# hacker-boards-refactor.net
KiCad netlist of a schematic drawn in EAGLE
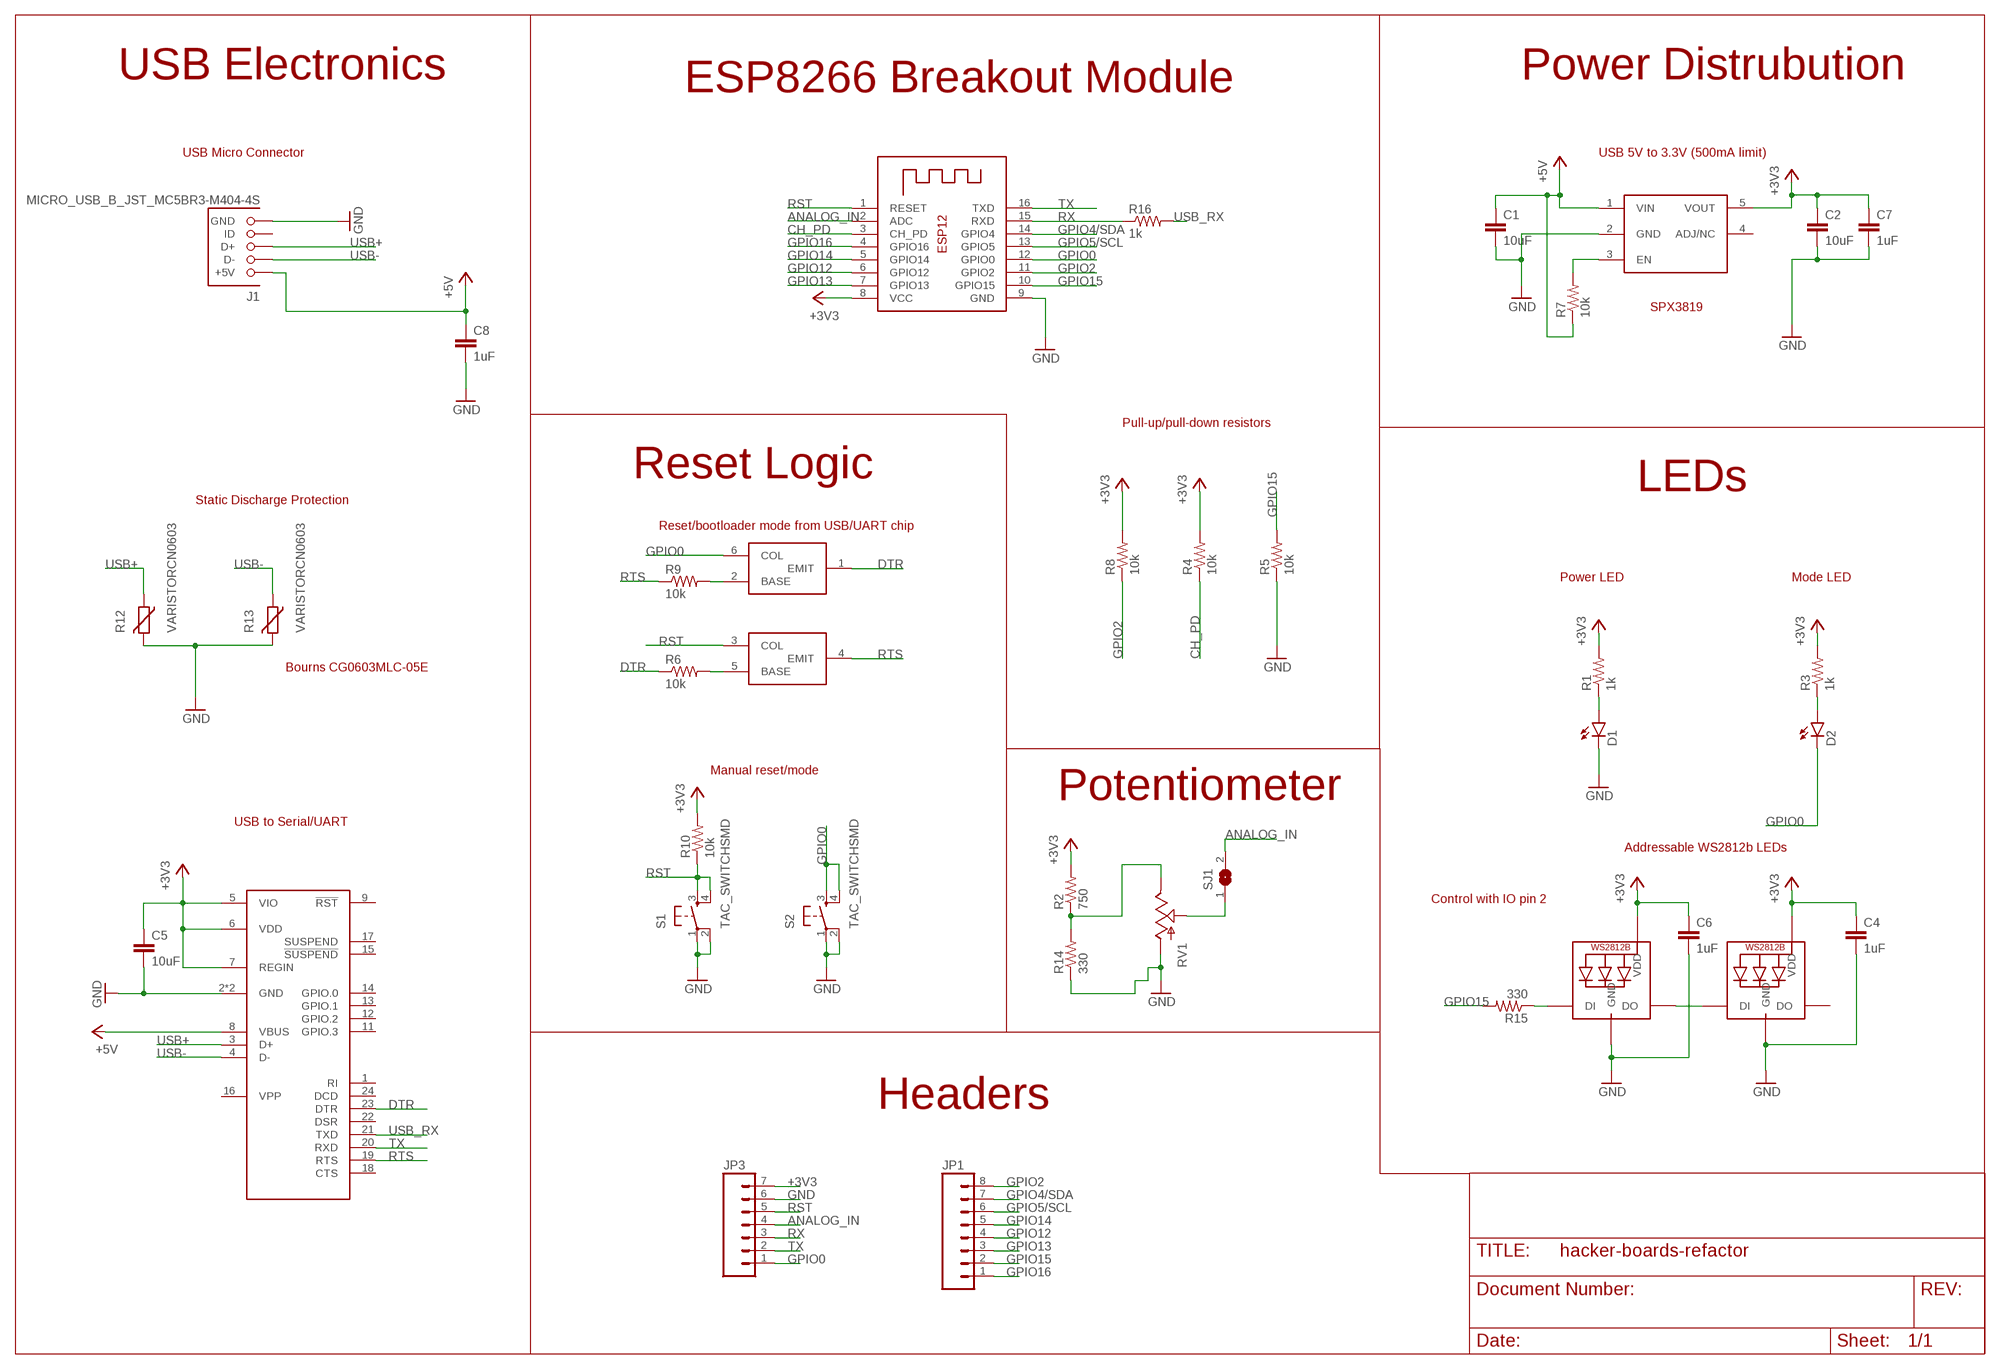
[diagram p0: schematic, sheet 1]

(export (version "E")
  (design (tool "Eeschema 10.0.6"))
  (components
    (comp (ref "C1")
      (value "10uF")
      (footprint "eagle-import:C0805")
      (libsource (lib "eagle-import") (part "C0805"))
    )
    (comp (ref "C2")
      (value "10uF")
      (footprint "eagle-import:C0805")
      (libsource (lib "eagle-import") (part "C0805"))
    )
    (comp (ref "C4")
      (value "1uF")
      (footprint "eagle-import:C0402")
      (libsource (lib "eagle-import") (part "C-EUC0402"))
    )
    (comp (ref "C5")
      (value "10uF")
      (footprint "eagle-import:C0805")
      (libsource (lib "eagle-import") (part "C0805"))
    )
    (comp (ref "C6")
      (value "1uF")
      (footprint "eagle-import:C0402")
      (libsource (lib "eagle-import") (part "C-EUC0402"))
    )
    (comp (ref "C7")
      (value "1uF")
      (footprint "eagle-import:C0402")
      (libsource (lib "eagle-import") (part "C-EUC0402"))
    )
    (comp (ref "C8")
      (value "1uF")
      (footprint "eagle-import:C0402")
      (libsource (lib "eagle-import") (part "C-EUC0402"))
    )
    (comp (ref "D1")
      (value "LED0603")
      (footprint "eagle-import:LED-0603")
      (libsource (lib "eagle-import") (part "LED0603"))
    )
    (comp (ref "D2")
      (value "LED0603")
      (footprint "eagle-import:LED-0603")
      (libsource (lib "eagle-import") (part "LED0603"))
    )
    (comp (ref "J1")
      (value "MICRO_USB_B_JST_MC5BR3-M404-4S")
      (footprint "eagle-import:USB_MICRO_B-JST-MC5BR3-M404-4S-TB")
      (libsource (lib "eagle-import") (part "MICRO_USB_B_JST_MC5BR3-M404-4S"))
    )
    (comp (ref "JP1")
      (value "M08")
      (footprint "eagle-import:1X08_ROUND")
      (libsource (lib "eagle-import") (part "M08"))
    )
    (comp (ref "JP3")
      (value "M07")
      (footprint "eagle-import:1X07")
      (libsource (lib "eagle-import") (part "M07"))
    )
    (comp (ref "LED1")
      (value "WS2812B5050")
      (footprint "eagle-import:WS2812B")
      (libsource (lib "eagle-import") (part "WS2812B5050"))
    )
    (comp (ref "LED2")
      (value "WS2812B5050")
      (footprint "eagle-import:WS2812B")
      (libsource (lib "eagle-import") (part "WS2812B5050"))
    )
    (comp (ref "R1")
      (value "1k")
      (footprint "eagle-import:R0402")
      (libsource (lib "eagle-import") (part "R-US_R0402"))
    )
    (comp (ref "R2")
      (value "750")
      (footprint "eagle-import:R0402")
      (libsource (lib "eagle-import") (part "R-US_R0402"))
    )
    (comp (ref "R3")
      (value "1k")
      (footprint "eagle-import:R0402")
      (libsource (lib "eagle-import") (part "R-US_R0402"))
    )
    (comp (ref "R4")
      (value "10k")
      (footprint "eagle-import:R0402")
      (libsource (lib "eagle-import") (part "R-US_R0402"))
    )
    (comp (ref "R5")
      (value "10k")
      (footprint "eagle-import:R0402")
      (libsource (lib "eagle-import") (part "R-US_R0402"))
    )
    (comp (ref "R6")
      (value "10k")
      (footprint "eagle-import:R0402")
      (libsource (lib "eagle-import") (part "R-US_R0402"))
    )
    (comp (ref "R7")
      (value "10k")
      (footprint "eagle-import:R0402")
      (libsource (lib "eagle-import") (part "R-US_R0402"))
    )
    (comp (ref "R8")
      (value "10k")
      (footprint "eagle-import:R0402")
      (libsource (lib "eagle-import") (part "R-US_R0402"))
    )
    (comp (ref "R9")
      (value "10k")
      (footprint "eagle-import:R0402")
      (libsource (lib "eagle-import") (part "R-US_R0402"))
    )
    (comp (ref "R10")
      (value "10k")
      (footprint "eagle-import:R0402")
      (libsource (lib "eagle-import") (part "R-US_R0402"))
    )
    (comp (ref "R12")
      (value "VARISTORCN0603")
      (footprint "eagle-import:CT_CN0603")
      (libsource (lib "eagle-import") (part "VARISTORCN0603"))
    )
    (comp (ref "R13")
      (value "VARISTORCN0603")
      (footprint "eagle-import:CT_CN0603")
      (libsource (lib "eagle-import") (part "VARISTORCN0603"))
    )
    (comp (ref "R14")
      (value "330")
      (footprint "eagle-import:R0402")
      (libsource (lib "eagle-import") (part "R-US_R0402"))
    )
    (comp (ref "R15")
      (value "330")
      (footprint "eagle-import:R0402")
      (libsource (lib "eagle-import") (part "R-US_R0402"))
    )
    (comp (ref "R16")
      (value "1k")
      (footprint "eagle-import:R0402")
      (libsource (lib "eagle-import") (part "R-US_R0402"))
    )
    (comp (ref "RV1")
      (value "POTALPS-KIT")
      (footprint "eagle-import:ALPS_POT_KIT")
      (libsource (lib "eagle-import") (part "POTALPS-KIT"))
    )
    (comp (ref "S1")
      (value "TAC_SWITCHSMD")
      (footprint "eagle-import:TACTILE-SWITCH-SMD")
      (libsource (lib "eagle-import") (part "TAC_SWITCHSMD"))
    )
    (comp (ref "S2")
      (value "TAC_SWITCHSMD")
      (footprint "eagle-import:TACTILE-SWITCH-SMD")
      (libsource (lib "eagle-import") (part "TAC_SWITCHSMD"))
    )
    (comp (ref "SJ1") (value "SJ") (footprint "eagle-import:SJ") (libsource (lib "eagle-import") (part "SJ")))
    (comp (ref "U$2")
      (value "AP2112")
      (footprint "eagle-import:SOT23-5L")
      (libsource (lib "eagle-import") (part "AP2112"))
    )
    (comp (ref "U$3")
      (value "CP2104")
      (footprint "eagle-import:QFN24_4X4")
      (libsource (lib "eagle-import") (part "CP2104"))
    )
    (comp (ref "U$4")
      (value "MBT3904DW1T1G")
      (footprint "eagle-import:SOT363")
      (libsource (lib "eagle-import") (part "MBT3904DW1T1G"))
    )
    (comp (ref "X1")
      (value "ESP-12")
      (footprint "eagle-import:ESP-12")
      (libsource (lib "eagle-import") (part "ESP-12"))
    )
  )
  (nets
    (net (code "1") (name "+3V3") (class "Default")
      (node (ref "C2") (pin "1") (pinfunction "1_1") (pintype "passive"))
      (node (ref "C4") (pin "1") (pinfunction "1_1") (pintype "passive"))
      (node (ref "C5") (pin "1") (pinfunction "1_1") (pintype "passive"))
      (node (ref "C6") (pin "1") (pinfunction "1_1") (pintype "passive"))
      (node (ref "C7") (pin "1") (pinfunction "1_1") (pintype "passive"))
      (node (ref "JP3") (pin "7") (pinfunction "7_7") (pintype "passive"))
      (node (ref "LED1") (pin "1-VDD") (pinfunction "VDD_1-VDD") (pintype "power_in"))
      (node (ref "LED2") (pin "1-VDD") (pinfunction "VDD_1-VDD") (pintype "power_in"))
      (node (ref "R1") (pin "2") (pinfunction "2_2") (pintype "passive"))
      (node (ref "R10") (pin "2") (pinfunction "2_2") (pintype "passive"))
      (node (ref "R2") (pin "2") (pinfunction "2_2") (pintype "passive"))
      (node (ref "R3") (pin "2") (pinfunction "2_2") (pintype "passive"))
      (node (ref "R4") (pin "2") (pinfunction "2_2") (pintype "passive"))
      (node (ref "R8") (pin "2") (pinfunction "2_2") (pintype "passive"))
      (node (ref "U$2") (pin "5") (pinfunction "VOUT_5") (pintype "bidirectional"))
      (node (ref "U$3") (pin "5") (pinfunction "VIO_5") (pintype "bidirectional"))
      (node (ref "U$3") (pin "6") (pinfunction "VDD_6") (pintype "bidirectional"))
      (node (ref "U$3") (pin "7") (pinfunction "REGIN_7") (pintype "bidirectional"))
      (node (ref "X1") (pin "8") (pinfunction "VCC_8") (pintype "power_in"))
    )
    (net (code "2") (name "+5V") (class "Default")
      (node (ref "C1") (pin "1") (pinfunction "1_1") (pintype "passive"))
      (node (ref "C8") (pin "1") (pinfunction "1_1") (pintype "passive"))
      (node (ref "J1") (pin "1") (pinfunction "+5V_1") (pintype "bidirectional"))
      (node (ref "R7") (pin "1") (pinfunction "1_1") (pintype "passive"))
      (node (ref "U$2") (pin "1") (pinfunction "VIN_1") (pintype "bidirectional"))
      (node (ref "U$3") (pin "8") (pinfunction "VBUS_8") (pintype "bidirectional"))
    )
    (net (code "3") (name "/ANALOG_IN") (class "Default")
      (node (ref "JP3") (pin "4") (pinfunction "4_4") (pintype "passive"))
      (node (ref "SJ1") (pin "2") (pinfunction "2_2") (pintype "passive"))
      (node (ref "X1") (pin "2") (pinfunction "ADC_2") (pintype "passive"))
    )
    (net (code "4") (name "/CH_PD") (class "Default")
      (node (ref "R4") (pin "1") (pinfunction "1_1") (pintype "passive"))
      (node (ref "X1") (pin "3") (pinfunction "CH_PD_3") (pintype "input"))
    )
    (net (code "5") (name "/DTR") (class "Default")
      (node (ref "R6") (pin "1") (pinfunction "1_1") (pintype "passive"))
      (node (ref "U$3") (pin "23") (pinfunction "DTR_23") (pintype "bidirectional"))
      (node (ref "U$4") (pin "1") (pinfunction "EMIT_1") (pintype "bidirectional"))
    )
    (net (code "6") (name "/GPIO0") (class "Default")
      (node (ref "D2") (pin "C") (pinfunction "C_C") (pintype "passive"))
      (node (ref "JP3") (pin "1") (pinfunction "1_1") (pintype "passive"))
      (node (ref "S2") (pin "3") (pinfunction "3_3") (pintype "passive"))
      (node (ref "S2") (pin "4") (pinfunction "4_4") (pintype "passive"))
      (node (ref "U$4") (pin "6") (pinfunction "COL_6") (pintype "bidirectional"))
      (node (ref "X1") (pin "12") (pinfunction "GPIO0_12") (pintype "bidirectional"))
    )
    (net (code "7") (name "/GPIO2") (class "Default")
      (node (ref "JP1") (pin "8") (pinfunction "8_8") (pintype "passive"))
      (node (ref "R8") (pin "1") (pinfunction "1_1") (pintype "passive"))
      (node (ref "X1") (pin "11") (pinfunction "GPIO2_11") (pintype "bidirectional"))
    )
    (net (code "8") (name "/GPIO4{slash}SDA") (class "Default")
      (node (ref "JP1") (pin "7") (pinfunction "7_7") (pintype "passive"))
      (node (ref "X1") (pin "14") (pinfunction "GPIO4_14") (pintype "bidirectional"))
    )
    (net (code "9") (name "/GPIO5{slash}SCL") (class "Default")
      (node (ref "JP1") (pin "6") (pinfunction "6_6") (pintype "passive"))
      (node (ref "X1") (pin "13") (pinfunction "GPIO5_13") (pintype "bidirectional"))
    )
    (net (code "10") (name "/GPIO12") (class "Default")
      (node (ref "JP1") (pin "4") (pinfunction "4_4") (pintype "passive"))
      (node (ref "X1") (pin "6") (pinfunction "GPIO12_6") (pintype "bidirectional"))
    )
    (net (code "11") (name "/GPIO13") (class "Default")
      (node (ref "JP1") (pin "3") (pinfunction "3_3") (pintype "passive"))
      (node (ref "X1") (pin "7") (pinfunction "GPIO13_7") (pintype "bidirectional"))
    )
    (net (code "12") (name "/GPIO14") (class "Default")
      (node (ref "JP1") (pin "5") (pinfunction "5_5") (pintype "passive"))
      (node (ref "X1") (pin "5") (pinfunction "GPIO14_5") (pintype "bidirectional"))
    )
    (net (code "13") (name "/GPIO15") (class "Default")
      (node (ref "JP1") (pin "2") (pinfunction "2_2") (pintype "passive"))
      (node (ref "R15") (pin "2") (pinfunction "2_2") (pintype "passive"))
      (node (ref "R5") (pin "2") (pinfunction "2_2") (pintype "passive"))
      (node (ref "X1") (pin "10") (pinfunction "GPIO15_10") (pintype "bidirectional"))
    )
    (net (code "14") (name "/GPIO16") (class "Default")
      (node (ref "JP1") (pin "1") (pinfunction "1_1") (pintype "passive"))
      (node (ref "X1") (pin "4") (pinfunction "GPIO16_4") (pintype "bidirectional"))
    )
    (net (code "15") (name "/RST") (class "Default")
      (node (ref "JP3") (pin "5") (pinfunction "5_5") (pintype "passive"))
      (node (ref "R10") (pin "1") (pinfunction "1_1") (pintype "passive"))
      (node (ref "S1") (pin "3") (pinfunction "3_3") (pintype "passive"))
      (node (ref "S1") (pin "4") (pinfunction "4_4") (pintype "passive"))
      (node (ref "U$4") (pin "3") (pinfunction "COL_3") (pintype "bidirectional"))
      (node (ref "X1") (pin "1") (pinfunction "RESET_1") (pintype "input"))
    )
    (net (code "16") (name "/RTS") (class "Default")
      (node (ref "R9") (pin "1") (pinfunction "1_1") (pintype "passive"))
      (node (ref "U$3") (pin "19") (pinfunction "RTS_19") (pintype "bidirectional"))
      (node (ref "U$4") (pin "4") (pinfunction "EMIT_4") (pintype "bidirectional"))
    )
    (net (code "17") (name "/RX") (class "Default")
      (node (ref "JP3") (pin "3") (pinfunction "3_3") (pintype "passive"))
      (node (ref "R16") (pin "1") (pinfunction "1_1") (pintype "passive"))
      (node (ref "X1") (pin "15") (pinfunction "RXD_15") (pintype "input"))
    )
    (net (code "18") (name "/TX") (class "Default")
      (node (ref "JP3") (pin "2") (pinfunction "2_2") (pintype "passive"))
      (node (ref "U$3") (pin "20") (pinfunction "RXD_20") (pintype "bidirectional"))
      (node (ref "X1") (pin "16") (pinfunction "TXD_16") (pintype "output"))
    )
    (net (code "19") (name "/USB+") (class "Default")
      (node (ref "J1") (pin "3") (pinfunction "D+_3") (pintype "bidirectional"))
      (node (ref "R12") (pin "1") (pinfunction "1_1") (pintype "passive"))
      (node (ref "U$3") (pin "3") (pinfunction "D+_3") (pintype "bidirectional"))
    )
    (net (code "20") (name "/USB-") (class "Default")
      (node (ref "J1") (pin "2") (pinfunction "D-_2") (pintype "bidirectional"))
      (node (ref "R13") (pin "1") (pinfunction "1_1") (pintype "passive"))
      (node (ref "U$3") (pin "4") (pinfunction "D-_4") (pintype "bidirectional"))
    )
    (net (code "21") (name "/USB_RX") (class "Default")
      (node (ref "R16") (pin "2") (pinfunction "2_2") (pintype "passive"))
      (node (ref "U$3") (pin "21") (pinfunction "TXD_21") (pintype "bidirectional"))
    )
    (net (code "22") (name "GND") (class "Default")
      (node (ref "C1") (pin "2") (pinfunction "2_2") (pintype "passive"))
      (node (ref "C2") (pin "2") (pinfunction "2_2") (pintype "passive"))
      (node (ref "C4") (pin "2") (pinfunction "2_2") (pintype "passive"))
      (node (ref "C5") (pin "2") (pinfunction "2_2") (pintype "passive"))
      (node (ref "C6") (pin "2") (pinfunction "2_2") (pintype "passive"))
      (node (ref "C7") (pin "2") (pinfunction "2_2") (pintype "passive"))
      (node (ref "C8") (pin "2") (pinfunction "2_2") (pintype "passive"))
      (node (ref "D1") (pin "C") (pinfunction "C_C") (pintype "passive"))
      (node (ref "J1") (pin "5") (pinfunction "GND_5") (pintype "bidirectional"))
      (node (ref "JP3") (pin "6") (pinfunction "6_6") (pintype "passive"))
      (node (ref "LED1") (pin "3-GND") (pinfunction "GND_3-GND") (pintype "power_in"))
      (node (ref "LED2") (pin "3-GND") (pinfunction "GND_3-GND") (pintype "power_in"))
      (node (ref "R12") (pin "2") (pinfunction "2_2") (pintype "passive"))
      (node (ref "R13") (pin "2") (pinfunction "2_2") (pintype "passive"))
      (node (ref "R14") (pin "1") (pinfunction "1_1") (pintype "passive"))
      (node (ref "R5") (pin "1") (pinfunction "1_1") (pintype "passive"))
      (node (ref "RV1") (pin "P$3") (pinfunction "A_P$3") (pintype "passive"))
      (node (ref "S1") (pin "1") (pinfunction "1_1") (pintype "passive"))
      (node (ref "S1") (pin "2") (pinfunction "2_2") (pintype "passive"))
      (node (ref "S2") (pin "1") (pinfunction "1_1") (pintype "passive"))
      (node (ref "S2") (pin "2") (pinfunction "2_2") (pintype "passive"))
      (node (ref "U$2") (pin "2") (pinfunction "GND_2") (pintype "bidirectional"))
      (node (ref "U$3") (pin "2") (pinfunction "GND_2") (pintype "bidirectional"))
      (node (ref "U$3") (pin "25") (pinfunction "GND_25") (pintype "bidirectional"))
      (node (ref "X1") (pin "9") (pinfunction "GND_9") (pintype "power_in"))
    )
    (net (code "23") (name "Net-(D1-PadA)") (class "Default")
      (node (ref "D1") (pin "A") (pinfunction "A_A") (pintype "passive"))
      (node (ref "R1") (pin "1") (pinfunction "1_1") (pintype "passive"))
    )
    (net (code "24") (name "Net-(D2-PadA)") (class "Default")
      (node (ref "D2") (pin "A") (pinfunction "A_A") (pintype "passive"))
      (node (ref "R3") (pin "1") (pinfunction "1_1") (pintype "passive"))
    )
    (net (code "25") (name "Net-(LED1-DI)") (class "Default")
      (node (ref "LED1") (pin "4-DIN") (pinfunction "DI_4-DIN") (pintype "input"))
      (node (ref "R15") (pin "1") (pinfunction "1_1") (pintype "passive"))
    )
    (net (code "26") (name "Net-(LED1-DO)") (class "Default")
      (node (ref "LED1") (pin "2-DOUT") (pinfunction "DO_2-DOUT") (pintype "output"))
      (node (ref "LED2") (pin "4-DIN") (pinfunction "DI_4-DIN") (pintype "input"))
    )
    (net (code "27") (name "Net-(RV1-E)") (class "Default")
      (node (ref "R14") (pin "2") (pinfunction "2_2") (pintype "passive"))
      (node (ref "R2") (pin "1") (pinfunction "1_1") (pintype "passive"))
      (node (ref "RV1") (pin "P$1") (pinfunction "E_P$1") (pintype "passive"))
    )
    (net (code "28") (name "Net-(RV1-S)") (class "Default")
      (node (ref "RV1") (pin "P$2") (pinfunction "S_P$2") (pintype "passive"))
      (node (ref "SJ1") (pin "1") (pinfunction "1_1") (pintype "passive"))
    )
    (net (code "29") (name "Net-(U$2-EN)") (class "Default")
      (node (ref "R7") (pin "2") (pinfunction "2_2") (pintype "passive"))
      (node (ref "U$2") (pin "3") (pinfunction "EN_3") (pintype "bidirectional"))
    )
    (net (code "30") (name "Net-(U$4A-BASE)") (class "Default")
      (node (ref "R9") (pin "2") (pinfunction "2_2") (pintype "passive"))
      (node (ref "U$4") (pin "2") (pinfunction "BASE_2") (pintype "bidirectional"))
    )
    (net (code "31") (name "Net-(U$4B-BASE)") (class "Default")
      (node (ref "R6") (pin "2") (pinfunction "2_2") (pintype "passive"))
      (node (ref "U$4") (pin "5") (pinfunction "BASE_5") (pintype "bidirectional"))
    )
    (net (code "32") (name "unconnected-(J1-ID-Pad4)") (class "Default")
      (node (ref "J1") (pin "4") (pinfunction "ID_4") (pintype "bidirectional"))
    )
    (net (code "33") (name "unconnected-(LED2-DO-Pad2-DOUT)") (class "Default")
      (node (ref "LED2") (pin "2-DOUT") (pinfunction "DO_2-DOUT") (pintype "output"))
    )
    (net (code "34") (name "unconnected-(U$2-ADJ{slash}NC-Pad4)") (class "Default")
      (node (ref "U$2") (pin "4") (pinfunction "ADJ/NC_4") (pintype "bidirectional"))
    )
    (net (code "35") (name "unconnected-(U$3-CTS-Pad18)") (class "Default")
      (node (ref "U$3") (pin "18") (pinfunction "CTS_18") (pintype "bidirectional"))
    )
    (net (code "36") (name "unconnected-(U$3-DCD-Pad24)") (class "Default")
      (node (ref "U$3") (pin "24") (pinfunction "DCD_24") (pintype "bidirectional"))
    )
    (net (code "37") (name "unconnected-(U$3-DSR-Pad22)") (class "Default")
      (node (ref "U$3") (pin "22") (pinfunction "DSR_22") (pintype "bidirectional"))
    )
    (net (code "38") (name "unconnected-(U$3-GPIO.0-Pad14)") (class "Default")
      (node (ref "U$3") (pin "14") (pinfunction "GPIO.0_14") (pintype "bidirectional"))
    )
    (net (code "39") (name "unconnected-(U$3-GPIO.1-Pad13)") (class "Default")
      (node (ref "U$3") (pin "13") (pinfunction "GPIO.1_13") (pintype "bidirectional"))
    )
    (net (code "40") (name "unconnected-(U$3-GPIO.2-Pad12)") (class "Default")
      (node (ref "U$3") (pin "12") (pinfunction "GPIO.2_12") (pintype "bidirectional"))
    )
    (net (code "41") (name "unconnected-(U$3-GPIO.3-Pad11)") (class "Default")
      (node (ref "U$3") (pin "11") (pinfunction "GPIO.3_11") (pintype "bidirectional"))
    )
    (net (code "42") (name "unconnected-(U$3-RI-Pad1)") (class "Default")
      (node (ref "U$3") (pin "1") (pinfunction "RI_1") (pintype "bidirectional"))
    )
    (net (code "43") (name "unconnected-(U$3-SUSPEND-Pad17)") (class "Default")
      (node (ref "U$3") (pin "17") (pinfunction "SUSPEND_17") (pintype "bidirectional"))
    )
    (net (code "44") (name "unconnected-(U$3-VPP-Pad16)") (class "Default")
      (node (ref "U$3") (pin "16") (pinfunction "VPP_16") (pintype "input"))
    )
    (net (code "45") (name "unconnected-(U$3-~{RST}-Pad9)") (class "Default")
      (node (ref "U$3") (pin "9") (pinfunction "~{RST}_9") (pintype "bidirectional"))
    )
    (net (code "46") (name "unconnected-(U$3-~{SUSPEND}-Pad15)") (class "Default")
      (node (ref "U$3") (pin "15") (pinfunction "~{SUSPEND}_15") (pintype "bidirectional"))
    )
  )
)
